# gydrodrive_control.net
KiCad netlist of a schematic drawn in Altium Designer
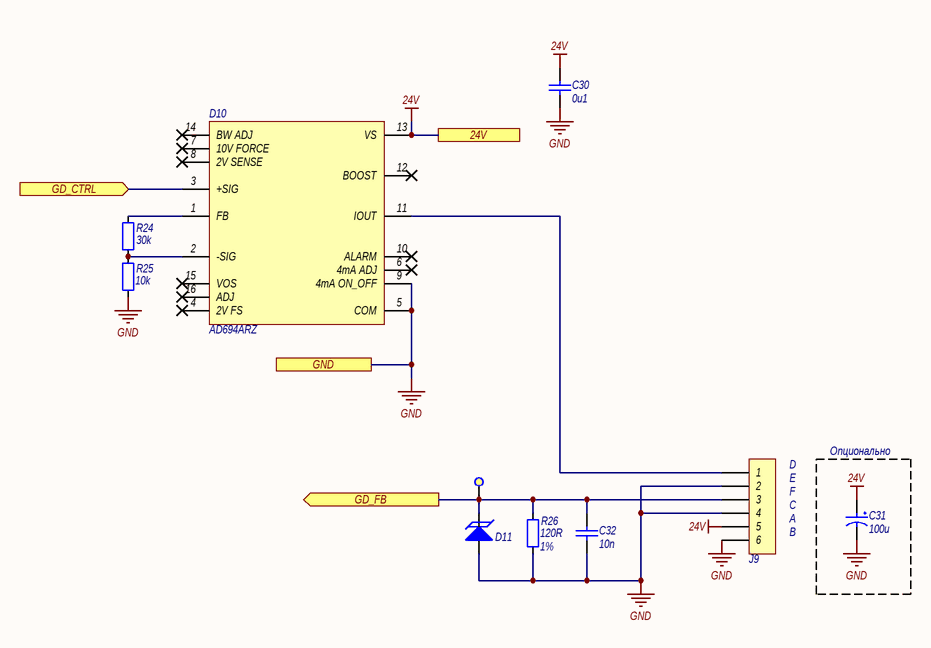
[diagram p0: gydrodrive_control.SchDoc]

(export (version "E")
  (design (tool "Eeschema 10.0.6"))
  (components
    (comp (ref "C30")
      (value "CAP_0805")
      (footprint "CAPC2012-0805M")
      (description "Конденсатор керамический, корпус 0805")
      (fields
        (field (name "CAPACITANCE") "0u1")
        (field (name "PART NUMBER") "CAPC_0805")
        (field (name "VOLTAGE") "50V")
      )
      (libsource (lib "StdLib") (part "CAP"))
    )
    (comp (ref "C31")
      (value "TKR101M1HF11")
      (footprint "ECAP811.5")
      (description "Конденсатор электролитический")
      (fields (field (name "CAPACITANCE") "100u") (field (name "VOLTAGE") "50V"))
      (libsource (lib "StdLib") (part "CAP_POL"))
    )
    (comp (ref "C32")
      (value "CAP_0805")
      (footprint "CAPC2012-0805M")
      (description "Конденсатор керамический, корпус 0805")
      (fields
        (field (name "CAPACITANCE") "10n")
        (field (name "PART NUMBER") "CAPC_0805")
        (field (name "VOLTAGE") "50V")
      )
      (libsource (lib "StdLib") (part "CAP"))
    )
    (comp (ref "D10") (value "AD694ARZ") (footprint "SO16W_M") (libsource (lib "StdLib") (part "AD694")))
    (comp (ref "D11")
      (value "SMBJ3V3-E3/52")
      (footprint "SMB_M")
      (description "Защитный диод (TVS)")
      (fields (field (name "VOLTAGE") "3V3"))
      (libsource (lib "StdLib") (part "TVS"))
    )
    (comp (ref "J9")
      (value "DG142V-5.08-06P")
      (footprint "DG142V-5.08-06P")
      (description "Клеммник 6-контактный, шаг 5.08 мм")
      (libsource (lib "StdLib") (part "PIN1x6"))
    )
    (comp (ref "R24")
      (value "RES_0805")
      (footprint "RESC2012-0805M")
      (description "Рез-р, корпус 0805")
      (fields
        (field (name "RESISTANCE") "30k")
        (field (name "PART NUMBER") "RESC_0805")
        (field (name "TOLERANCE") "5%")
      )
      (libsource (lib "StdLib") (part "RES"))
    )
    (comp (ref "R25")
      (value "RES_0805")
      (footprint "RESC2012-0805M")
      (description "Рез-р, корпус 0805")
      (fields
        (field (name "RESISTANCE") "10k")
        (field (name "PART NUMBER") "RESC_0805")
        (field (name "TOLERANCE") "5%")
      )
      (libsource (lib "StdLib") (part "RES"))
    )
    (comp (ref "R26")
      (value "RES_0805")
      (footprint "RESC2012-0805M")
      (description "Рез-р, корпус 0805")
      (fields
        (field (name "RESISTANCE") "120R")
        (field (name "PART NUMBER") "RESC_0805")
        (field (name "TOLERANCE") "1%")
      )
      (libsource (lib "StdLib") (part "RES"))
    )
    (comp (ref "TP8")
      (value "Test point 1")
      (footprint "TP_1")
      (description "Тестовый контакт круглый 1 мм")
      (libsource (lib "StdLib") (part "Test point"))
    )
  )
  (nets
    (net (code "1") (name "/GD_CTRL") (class "Default")
      (node (ref "D10") (pin "3") (pinfunction "+SIG_3") (pintype "passive"))
    )
    (net (code "2") (name "/GD_FB") (class "Default")
      (node (ref "C32") (pin "2") (pinfunction "2_2") (pintype "passive"))
      (node (ref "D11") (pin "1") (pinfunction "K_1") (pintype "passive"))
      (node (ref "J9") (pin "3") (pinfunction "3_3") (pintype "passive"))
      (node (ref "R26") (pin "2") (pinfunction "2_2") (pintype "passive"))
      (node (ref "TP8") (pin "1") (pinfunction "1_1") (pintype "passive"))
    )
    (net (code "3") (name "24V") (class "Default")
      (node (ref "C30") (pin "2") (pinfunction "2_2") (pintype "passive"))
      (node (ref "C31") (pin "1") (pinfunction "1_1") (pintype "passive"))
      (node (ref "D10") (pin "13") (pinfunction "VS_13") (pintype "passive"))
      (node (ref "J9") (pin "5") (pinfunction "5_5") (pintype "passive"))
    )
    (net (code "4") (name "GND") (class "Default")
      (node (ref "C30") (pin "1") (pinfunction "1_1") (pintype "passive"))
      (node (ref "C31") (pin "2") (pinfunction "2_2") (pintype "passive"))
      (node (ref "C32") (pin "1") (pinfunction "1_1") (pintype "passive"))
      (node (ref "D10") (pin "5") (pinfunction "COM_5") (pintype "passive"))
      (node (ref "D10") (pin "9") (pinfunction "4mA_ON_OFF_9") (pintype "passive"))
      (node (ref "D11") (pin "2") (pinfunction "A_2") (pintype "passive"))
      (node (ref "J9") (pin "2") (pinfunction "2_2") (pintype "passive"))
      (node (ref "J9") (pin "4") (pinfunction "4_4") (pintype "passive"))
      (node (ref "J9") (pin "6") (pinfunction "6_6") (pintype "passive"))
      (node (ref "R25") (pin "1") (pinfunction "1_1") (pintype "passive"))
      (node (ref "R26") (pin "1") (pinfunction "1_1") (pintype "passive"))
    )
    (net (code "5") (name "Net-(D10--SIG)") (class "Default")
      (node (ref "D10") (pin "2") (pinfunction "-SIG_2") (pintype "passive"))
      (node (ref "R24") (pin "1") (pinfunction "1_1") (pintype "passive"))
      (node (ref "R25") (pin "2") (pinfunction "2_2") (pintype "passive"))
    )
    (net (code "6") (name "Net-(D10-FB)") (class "Default")
      (node (ref "D10") (pin "1") (pinfunction "FB_1") (pintype "passive"))
      (node (ref "R24") (pin "2") (pinfunction "2_2") (pintype "passive"))
    )
    (net (code "7") (name "Net-(D10-IOUT)") (class "Default")
      (node (ref "D10") (pin "11") (pinfunction "IOUT_11") (pintype "passive"))
      (node (ref "J9") (pin "1") (pinfunction "1_1") (pintype "passive"))
    )
    (net (code "8") (name "unconnected-(D10-2V_FS-Pad4)") (class "Default")
      (node (ref "D10") (pin "4") (pinfunction "2V_FS_4") (pintype "passive+no_connect"))
    )
    (net (code "9") (name "unconnected-(D10-2V_SENSE-Pad8)") (class "Default")
      (node (ref "D10") (pin "8") (pinfunction "2V_SENSE_8") (pintype "passive+no_connect"))
    )
    (net (code "10") (name "unconnected-(D10-4mA_ADJ-Pad6)") (class "Default")
      (node (ref "D10") (pin "6") (pinfunction "4mA_ADJ_6") (pintype "passive+no_connect"))
    )
    (net (code "11") (name "unconnected-(D10-10V_FORCE-Pad7)") (class "Default")
      (node (ref "D10") (pin "7") (pinfunction "10V_FORCE_7") (pintype "passive+no_connect"))
    )
    (net (code "12") (name "unconnected-(D10-ADJ-Pad16)") (class "Default")
      (node (ref "D10") (pin "16") (pinfunction "ADJ_16") (pintype "passive+no_connect"))
    )
    (net (code "13") (name "unconnected-(D10-ALARM-Pad10)") (class "Default")
      (node (ref "D10") (pin "10") (pinfunction "ALARM_10") (pintype "passive+no_connect"))
    )
    (net (code "14") (name "unconnected-(D10-BOOST-Pad12)") (class "Default")
      (node (ref "D10") (pin "12") (pinfunction "BOOST_12") (pintype "passive+no_connect"))
    )
    (net (code "15") (name "unconnected-(D10-BW_ADJ-Pad14)") (class "Default")
      (node (ref "D10") (pin "14") (pinfunction "BW_ADJ_14") (pintype "passive+no_connect"))
    )
    (net (code "16") (name "unconnected-(D10-VOS-Pad15)") (class "Default")
      (node (ref "D10") (pin "15") (pinfunction "VOS_15") (pintype "passive+no_connect"))
    )
  )
)
